# AS91-Rel8TstAd-01.net
KiCad netlist of a schematic drawn in EAGLE
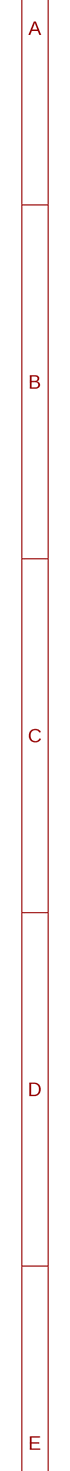
[diagram p0: schematic, sheet 1, part 1 of 2]
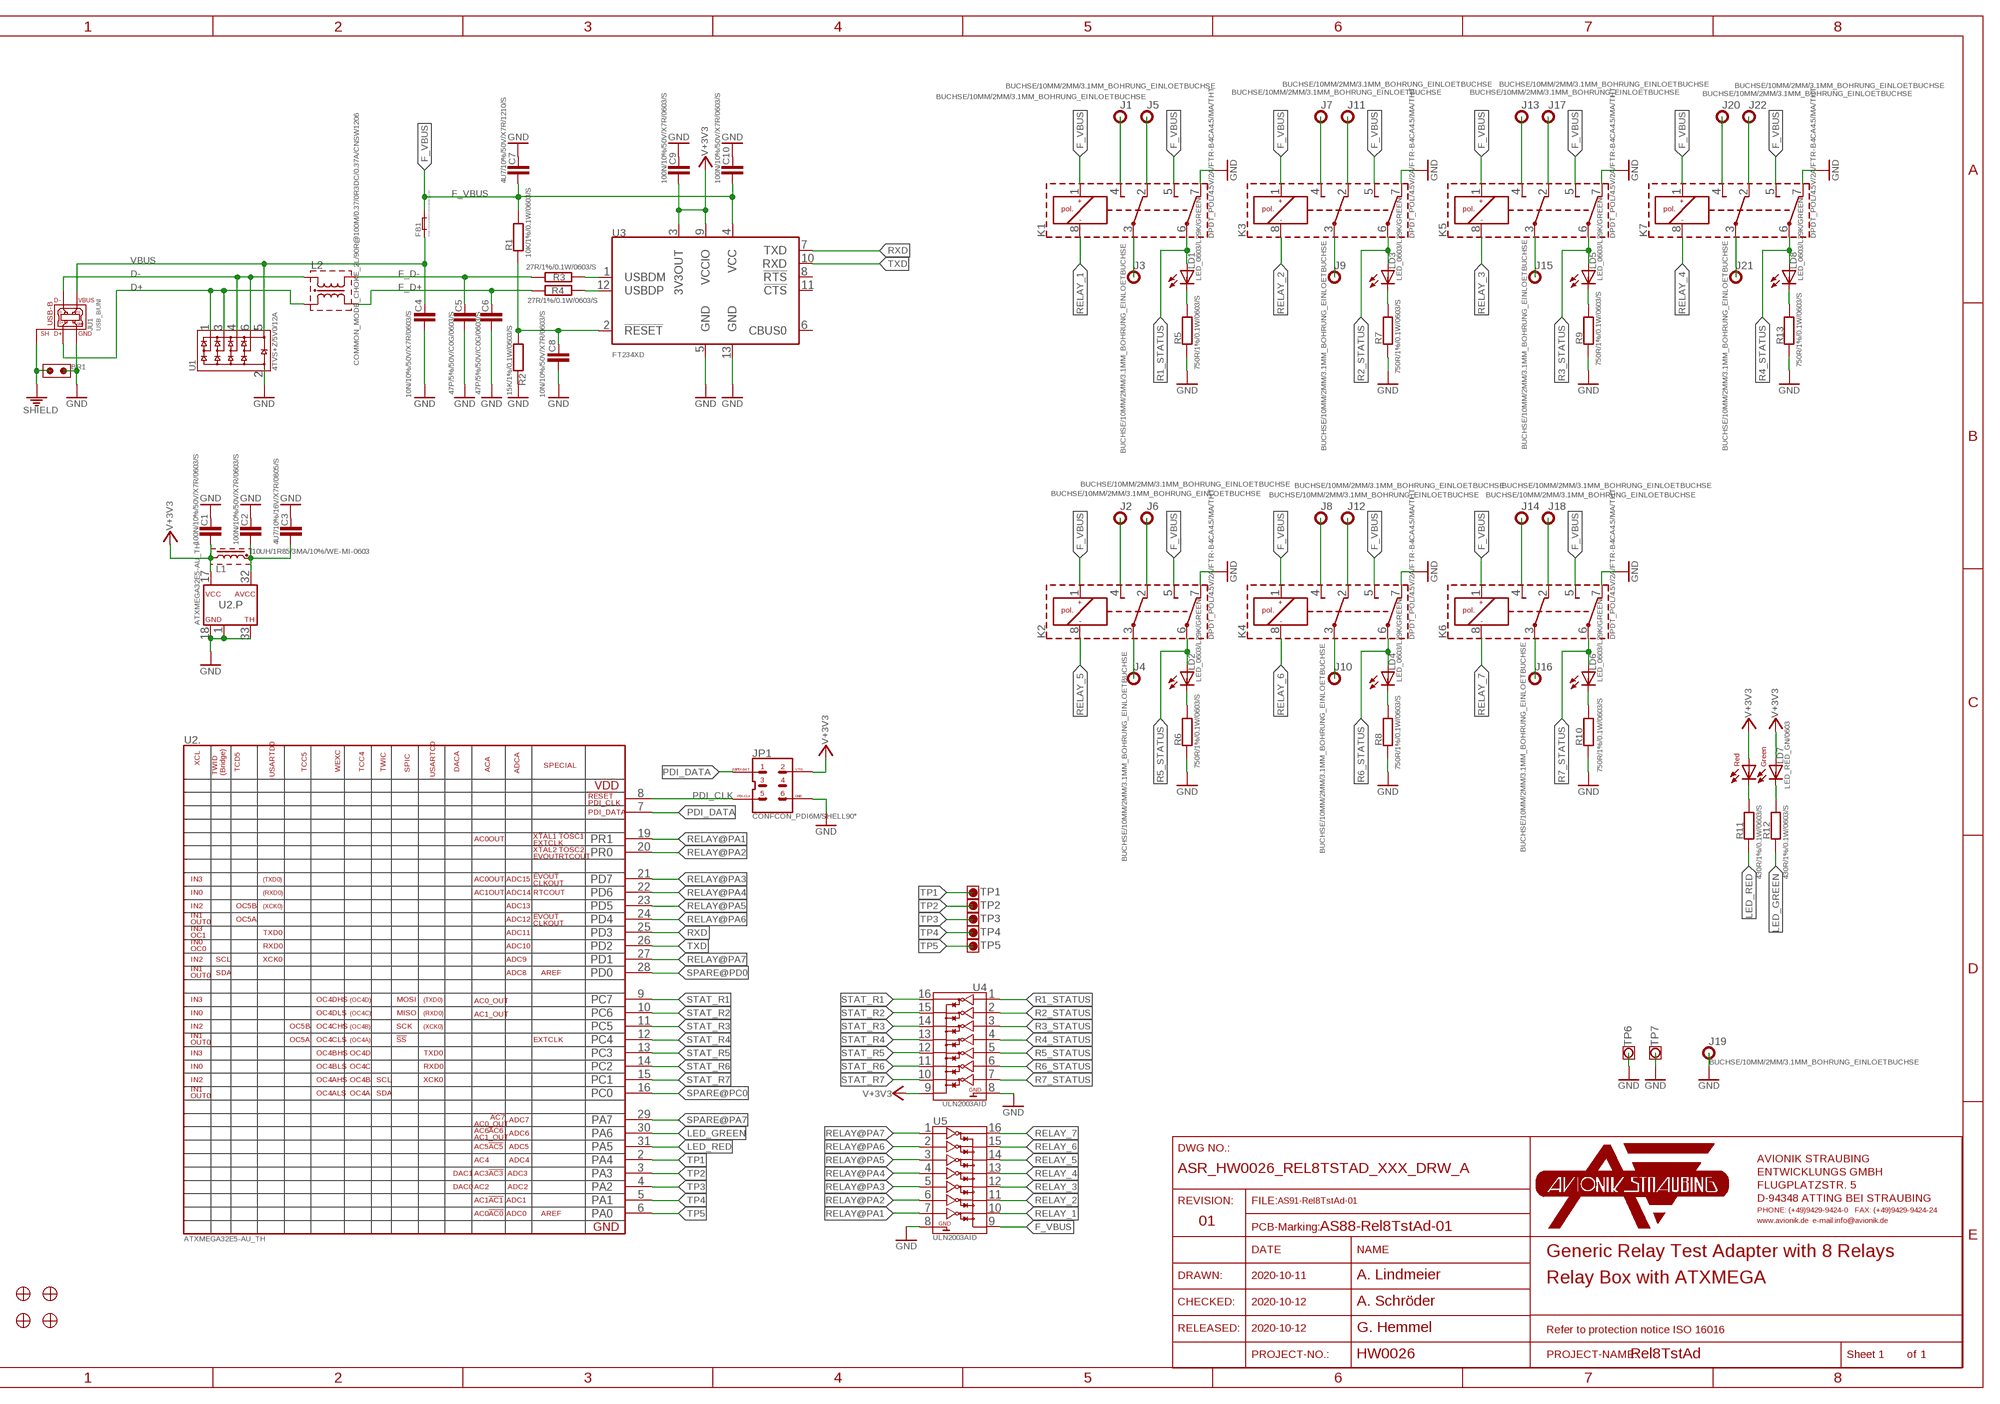
[diagram p1: schematic, sheet 1, part 2 of 2]

(export (version "E")
  (design (tool "Eeschema 10.0.6"))
  (components
    (comp (ref "BR1")
      (value "BRIDGE_OPEN/SOLDER")
      (footprint "eagle-import:SOLDER_OPEN")
      (libsource (lib "eagle-import") (part "BRIDGE_OPEN/SOLDER"))
    )
    (comp (ref "C1")
      (value "100N/10%/50V/X7R/0603/S")
      (footprint "eagle-import:C0603_STD")
      (fields (field (name "MFR") "Kemet, C0603C104K5RACTU"))
      (libsource (lib "eagle-import") (part "100N/0603/S/10%/50V/X7R"))
    )
    (comp (ref "C2")
      (value "100N/10%/50V/X7R/0603/S")
      (footprint "eagle-import:C0603_STD")
      (fields (field (name "MFR") "Kemet, C0603C104K5RACTU"))
      (libsource (lib "eagle-import") (part "100N/0603/S/10%/50V/X7R"))
    )
    (comp (ref "C3")
      (value "4U7/10%/16V/X7R/0805/S")
      (footprint "eagle-import:C0805_STD")
      (fields (field (name "MFR") "Kemet, C0805C475K4RACAUTO"))
      (libsource (lib "eagle-import") (part "4U7/0805/S/10%/16V/X7R"))
    )
    (comp (ref "C4")
      (value "10N/10%/50V/X7R/0603/S")
      (footprint "eagle-import:C0603_STD")
      (fields (field (name "MFR") "Kemet, C0603C103K5RACTU"))
      (libsource (lib "eagle-import") (part "10N/0603/S/10%/50V/X7R"))
    )
    (comp (ref "C5")
      (value "47P/5%/50V/C0G/0603/S")
      (footprint "eagle-import:C0603_STD")
      (fields (field (name "MFR") "Kemet, C0603C470J5GACAUTO"))
      (libsource (lib "eagle-import") (part "47P/0603/S/5%/50V/C0G"))
    )
    (comp (ref "C6")
      (value "47P/5%/50V/C0G/0603/S")
      (footprint "eagle-import:C0603_STD")
      (fields (field (name "MFR") "Kemet, C0603C470J5GACAUTO"))
      (libsource (lib "eagle-import") (part "47P/0603/S/5%/50V/C0G"))
    )
    (comp (ref "C7")
      (value "4U7/10%/50V/X7R/1210/S")
      (footprint "eagle-import:C1210_STD")
      (fields (field (name "MFR") "Kemet, C1210X475K5RACTU"))
      (libsource (lib "eagle-import") (part "4U7/1210/S/10%/50V/X7R"))
    )
    (comp (ref "C8")
      (value "10N/10%/50V/X7R/0603/S")
      (footprint "eagle-import:C0603_STD")
      (fields (field (name "MFR") "Kemet, C0603C103K5RACTU"))
      (libsource (lib "eagle-import") (part "10N/0603/S/10%/50V/X7R"))
    )
    (comp (ref "C9")
      (value "100N/10%/50V/X7R/0603/S")
      (footprint "eagle-import:C0603_STD")
      (fields (field (name "MFR") "Kemet, C0603C104K5RACTU"))
      (libsource (lib "eagle-import") (part "100N/0603/S/10%/50V/X7R"))
    )
    (comp (ref "C10")
      (value "100N/10%/50V/X7R/0603/S")
      (footprint "eagle-import:C0603_STD")
      (fields (field (name "MFR") "Kemet, C0603C104K5RACTU"))
      (libsource (lib "eagle-import") (part "100N/0603/S/10%/50V/X7R"))
    )
    (comp (ref "DRAWING_FRAME1")
      (value "DIN_A3LOC_PCBMARK_ASR/TOP/STOP/0.8")
      (footprint "eagle-import:FRAME_REVISION_TOP_STOP_0.8")
      (fields (field (name "PCB_MARKING") "AS88-Rel8TstAd-01"))
      (libsource (lib "eagle-import") (part "DIN_A3LOC_PCBMARK_ASR/TOP/STOP/0.8"))
    )
    (comp (ref "FB1")
      (value "FB/WE-CBF/742792620/DC0R15/0.5A/WE/CBF0603")
      (footprint "eagle-import:WE_CBF_0603")
      (fields (field (name "MFR") "Würth, 742792620"))
      (libsource (lib "eagle-import") (part "FB/WE/CBF0603/WE-CBF/742792620/DC0R15/0.5A"))
    )
    (comp (ref "J1")
      (value "BUCHSE/10MM/2MM/3.1MM_BOHRUNG_EINLOETBUCHSE")
      (footprint "eagle-import:BUCHSE2MM_PCB3.1MMDRILL")
      (fields (field (name "MFR") "MC/Stäubli, LB2-D"))
      (libsource (lib "eagle-import") (part "BUCHSE/2MM/3.1MM_BOHRUNG_EINLOETBUCHSE/10MM"))
    )
    (comp (ref "J2")
      (value "BUCHSE/10MM/2MM/3.1MM_BOHRUNG_EINLOETBUCHSE")
      (footprint "eagle-import:BUCHSE2MM_PCB3.1MMDRILL")
      (fields (field (name "MFR") "MC/Stäubli, LB2-D"))
      (libsource (lib "eagle-import") (part "BUCHSE/2MM/3.1MM_BOHRUNG_EINLOETBUCHSE/10MM"))
    )
    (comp (ref "J3")
      (value "BUCHSE/10MM/2MM/3.1MM_BOHRUNG_EINLOETBUCHSE")
      (footprint "eagle-import:BUCHSE2MM_PCB3.1MMDRILL")
      (fields (field (name "MFR") "MC/Stäubli, LB2-D"))
      (libsource (lib "eagle-import") (part "BUCHSE/2MM/3.1MM_BOHRUNG_EINLOETBUCHSE/10MM"))
    )
    (comp (ref "J4")
      (value "BUCHSE/10MM/2MM/3.1MM_BOHRUNG_EINLOETBUCHSE")
      (footprint "eagle-import:BUCHSE2MM_PCB3.1MMDRILL")
      (fields (field (name "MFR") "MC/Stäubli, LB2-D"))
      (libsource (lib "eagle-import") (part "BUCHSE/2MM/3.1MM_BOHRUNG_EINLOETBUCHSE/10MM"))
    )
    (comp (ref "J5")
      (value "BUCHSE/10MM/2MM/3.1MM_BOHRUNG_EINLOETBUCHSE")
      (footprint "eagle-import:BUCHSE2MM_PCB3.1MMDRILL")
      (fields (field (name "MFR") "MC/Stäubli, LB2-D"))
      (libsource (lib "eagle-import") (part "BUCHSE/2MM/3.1MM_BOHRUNG_EINLOETBUCHSE/10MM"))
    )
    (comp (ref "J6")
      (value "BUCHSE/10MM/2MM/3.1MM_BOHRUNG_EINLOETBUCHSE")
      (footprint "eagle-import:BUCHSE2MM_PCB3.1MMDRILL")
      (fields (field (name "MFR") "MC/Stäubli, LB2-D"))
      (libsource (lib "eagle-import") (part "BUCHSE/2MM/3.1MM_BOHRUNG_EINLOETBUCHSE/10MM"))
    )
    (comp (ref "J7")
      (value "BUCHSE/10MM/2MM/3.1MM_BOHRUNG_EINLOETBUCHSE")
      (footprint "eagle-import:BUCHSE2MM_PCB3.1MMDRILL")
      (fields (field (name "MFR") "MC/Stäubli, LB2-D"))
      (libsource (lib "eagle-import") (part "BUCHSE/2MM/3.1MM_BOHRUNG_EINLOETBUCHSE/10MM"))
    )
    (comp (ref "J8")
      (value "BUCHSE/10MM/2MM/3.1MM_BOHRUNG_EINLOETBUCHSE")
      (footprint "eagle-import:BUCHSE2MM_PCB3.1MMDRILL")
      (fields (field (name "MFR") "MC/Stäubli, LB2-D"))
      (libsource (lib "eagle-import") (part "BUCHSE/2MM/3.1MM_BOHRUNG_EINLOETBUCHSE/10MM"))
    )
    (comp (ref "J9")
      (value "BUCHSE/10MM/2MM/3.1MM_BOHRUNG_EINLOETBUCHSE")
      (footprint "eagle-import:BUCHSE2MM_PCB3.1MMDRILL")
      (fields (field (name "MFR") "MC/Stäubli, LB2-D"))
      (libsource (lib "eagle-import") (part "BUCHSE/2MM/3.1MM_BOHRUNG_EINLOETBUCHSE/10MM"))
    )
    (comp (ref "J10")
      (value "BUCHSE/10MM/2MM/3.1MM_BOHRUNG_EINLOETBUCHSE")
      (footprint "eagle-import:BUCHSE2MM_PCB3.1MMDRILL")
      (fields (field (name "MFR") "MC/Stäubli, LB2-D"))
      (libsource (lib "eagle-import") (part "BUCHSE/2MM/3.1MM_BOHRUNG_EINLOETBUCHSE/10MM"))
    )
    (comp (ref "J11")
      (value "BUCHSE/10MM/2MM/3.1MM_BOHRUNG_EINLOETBUCHSE")
      (footprint "eagle-import:BUCHSE2MM_PCB3.1MMDRILL")
      (fields (field (name "MFR") "MC/Stäubli, LB2-D"))
      (libsource (lib "eagle-import") (part "BUCHSE/2MM/3.1MM_BOHRUNG_EINLOETBUCHSE/10MM"))
    )
    (comp (ref "J12")
      (value "BUCHSE/10MM/2MM/3.1MM_BOHRUNG_EINLOETBUCHSE")
      (footprint "eagle-import:BUCHSE2MM_PCB3.1MMDRILL")
      (fields (field (name "MFR") "MC/Stäubli, LB2-D"))
      (libsource (lib "eagle-import") (part "BUCHSE/2MM/3.1MM_BOHRUNG_EINLOETBUCHSE/10MM"))
    )
    (comp (ref "J13")
      (value "BUCHSE/10MM/2MM/3.1MM_BOHRUNG_EINLOETBUCHSE")
      (footprint "eagle-import:BUCHSE2MM_PCB3.1MMDRILL")
      (fields (field (name "MFR") "MC/Stäubli, LB2-D"))
      (libsource (lib "eagle-import") (part "BUCHSE/2MM/3.1MM_BOHRUNG_EINLOETBUCHSE/10MM"))
    )
    (comp (ref "J14")
      (value "BUCHSE/10MM/2MM/3.1MM_BOHRUNG_EINLOETBUCHSE")
      (footprint "eagle-import:BUCHSE2MM_PCB3.1MMDRILL")
      (fields (field (name "MFR") "MC/Stäubli, LB2-D"))
      (libsource (lib "eagle-import") (part "BUCHSE/2MM/3.1MM_BOHRUNG_EINLOETBUCHSE/10MM"))
    )
    (comp (ref "J15")
      (value "BUCHSE/10MM/2MM/3.1MM_BOHRUNG_EINLOETBUCHSE")
      (footprint "eagle-import:BUCHSE2MM_PCB3.1MMDRILL")
      (fields (field (name "MFR") "MC/Stäubli, LB2-D"))
      (libsource (lib "eagle-import") (part "BUCHSE/2MM/3.1MM_BOHRUNG_EINLOETBUCHSE/10MM"))
    )
    (comp (ref "J16")
      (value "BUCHSE/10MM/2MM/3.1MM_BOHRUNG_EINLOETBUCHSE")
      (footprint "eagle-import:BUCHSE2MM_PCB3.1MMDRILL")
      (fields (field (name "MFR") "MC/Stäubli, LB2-D"))
      (libsource (lib "eagle-import") (part "BUCHSE/2MM/3.1MM_BOHRUNG_EINLOETBUCHSE/10MM"))
    )
    (comp (ref "J17")
      (value "BUCHSE/10MM/2MM/3.1MM_BOHRUNG_EINLOETBUCHSE")
      (footprint "eagle-import:BUCHSE2MM_PCB3.1MMDRILL")
      (fields (field (name "MFR") "MC/Stäubli, LB2-D"))
      (libsource (lib "eagle-import") (part "BUCHSE/2MM/3.1MM_BOHRUNG_EINLOETBUCHSE/10MM"))
    )
    (comp (ref "J18")
      (value "BUCHSE/10MM/2MM/3.1MM_BOHRUNG_EINLOETBUCHSE")
      (footprint "eagle-import:BUCHSE2MM_PCB3.1MMDRILL")
      (fields (field (name "MFR") "MC/Stäubli, LB2-D"))
      (libsource (lib "eagle-import") (part "BUCHSE/2MM/3.1MM_BOHRUNG_EINLOETBUCHSE/10MM"))
    )
    (comp (ref "J19")
      (value "BUCHSE/10MM/2MM/3.1MM_BOHRUNG_EINLOETBUCHSE")
      (footprint "eagle-import:BUCHSE2MM_PCB3.1MMDRILL")
      (fields (field (name "MFR") "MC/Stäubli, LB2-D"))
      (libsource (lib "eagle-import") (part "BUCHSE/2MM/3.1MM_BOHRUNG_EINLOETBUCHSE/10MM"))
    )
    (comp (ref "J20")
      (value "BUCHSE/10MM/2MM/3.1MM_BOHRUNG_EINLOETBUCHSE")
      (footprint "eagle-import:BUCHSE2MM_PCB3.1MMDRILL")
      (fields (field (name "MFR") "MC/Stäubli, LB2-D"))
      (libsource (lib "eagle-import") (part "BUCHSE/2MM/3.1MM_BOHRUNG_EINLOETBUCHSE/10MM"))
    )
    (comp (ref "J21")
      (value "BUCHSE/10MM/2MM/3.1MM_BOHRUNG_EINLOETBUCHSE")
      (footprint "eagle-import:BUCHSE2MM_PCB3.1MMDRILL")
      (fields (field (name "MFR") "MC/Stäubli, LB2-D"))
      (libsource (lib "eagle-import") (part "BUCHSE/2MM/3.1MM_BOHRUNG_EINLOETBUCHSE/10MM"))
    )
    (comp (ref "J22")
      (value "BUCHSE/10MM/2MM/3.1MM_BOHRUNG_EINLOETBUCHSE")
      (footprint "eagle-import:BUCHSE2MM_PCB3.1MMDRILL")
      (fields (field (name "MFR") "MC/Stäubli, LB2-D"))
      (libsource (lib "eagle-import") (part "BUCHSE/2MM/3.1MM_BOHRUNG_EINLOETBUCHSE/10MM"))
    )
    (comp (ref "JP1")
      (value "CONFCON_PDI6M/SHELL90°")
      (footprint "eagle-import:PH2X3_WSL_SHELL_90°")
      (fields (field (name "MFR") "Molex, 90130-3106"))
      (libsource (lib "eagle-import") (part "CONFCON_PDI6M/SHELL90°"))
    )
    (comp (ref "JU1")
      (value "USB_B/UNI")
      (footprint "eagle-import:USB-B-BUCHSE-LP")
      (fields (field (name "MFR") "Amphenol, 61729-0010BLF"))
      (libsource (lib "eagle-import") (part "USB_B/UNI"))
    )
    (comp (ref "K1")
      (value "DPDT_POL/4.5V/2A/FTR-B4CA4.5/MA/THT")
      (footprint "eagle-import:FTR-B4")
      (fields (field (name "MFR") "Fujitsu-Takamisawa, FTR-B4CA4.5"))
      (libsource (lib "eagle-import") (part "DPDT_POL/MA/THT/4.5V/2A/FTR-B4CA4.5"))
    )
    (comp (ref "K2")
      (value "DPDT_POL/4.5V/2A/FTR-B4CA4.5/MA/THT")
      (footprint "eagle-import:FTR-B4")
      (fields (field (name "MFR") "Fujitsu-Takamisawa, FTR-B4CA4.5"))
      (libsource (lib "eagle-import") (part "DPDT_POL/MA/THT/4.5V/2A/FTR-B4CA4.5"))
    )
    (comp (ref "K3")
      (value "DPDT_POL/4.5V/2A/FTR-B4CA4.5/MA/THT")
      (footprint "eagle-import:FTR-B4")
      (fields (field (name "MFR") "Fujitsu-Takamisawa, FTR-B4CA4.5"))
      (libsource (lib "eagle-import") (part "DPDT_POL/MA/THT/4.5V/2A/FTR-B4CA4.5"))
    )
    (comp (ref "K4")
      (value "DPDT_POL/4.5V/2A/FTR-B4CA4.5/MA/THT")
      (footprint "eagle-import:FTR-B4")
      (fields (field (name "MFR") "Fujitsu-Takamisawa, FTR-B4CA4.5"))
      (libsource (lib "eagle-import") (part "DPDT_POL/MA/THT/4.5V/2A/FTR-B4CA4.5"))
    )
    (comp (ref "K5")
      (value "DPDT_POL/4.5V/2A/FTR-B4CA4.5/MA/THT")
      (footprint "eagle-import:FTR-B4")
      (fields (field (name "MFR") "Fujitsu-Takamisawa, FTR-B4CA4.5"))
      (libsource (lib "eagle-import") (part "DPDT_POL/MA/THT/4.5V/2A/FTR-B4CA4.5"))
    )
    (comp (ref "K6")
      (value "DPDT_POL/4.5V/2A/FTR-B4CA4.5/MA/THT")
      (footprint "eagle-import:FTR-B4")
      (fields (field (name "MFR") "Fujitsu-Takamisawa, FTR-B4CA4.5"))
      (libsource (lib "eagle-import") (part "DPDT_POL/MA/THT/4.5V/2A/FTR-B4CA4.5"))
    )
    (comp (ref "K7")
      (value "DPDT_POL/4.5V/2A/FTR-B4CA4.5/MA/THT")
      (footprint "eagle-import:FTR-B4")
      (fields (field (name "MFR") "Fujitsu-Takamisawa, FTR-B4CA4.5"))
      (libsource (lib "eagle-import") (part "DPDT_POL/MA/THT/4.5V/2A/FTR-B4CA4.5"))
    )
    (comp (ref "L1")
      (value "10UH/1R85/3MA/10%/WE-MI-0603")
      (footprint "eagle-import:WE-MI_0603")
      (fields (field (name "MFR") "Würth, 7447968"))
      (libsource (lib "eagle-import") (part "10UH/WE-MI-0603/1R85/3MA/10%"))
    )
    (comp (ref "L2")
      (value "COMMON_MODE_CHOKE_2L/90R@100M/0.37/0R3DC/0.37A/CNSW1206")
      (footprint "eagle-import:WUERTH_CNSW_1206")
      (fields (field (name "MFR") "Würth, 744232090"))
      (libsource (lib "eagle-import") (part "COMMON_MODE_CHOKE_2L/CNSW1206/90R@100M/0.37/0R3DC/0.37A"))
    )
    (comp (ref "LD1")
      (value "LED_0603/L29K/GREEN")
      (footprint "eagle-import:CHIPLED0603SMALL")
      (fields (field (name "MFR") "Osram, LG L29K-F2J1-24-Z"))
      (libsource (lib "eagle-import") (part "LED_0603/L29K/GREEN"))
    )
    (comp (ref "LD2")
      (value "LED_0603/L29K/GREEN")
      (footprint "eagle-import:CHIPLED0603SMALL")
      (fields (field (name "MFR") "Osram, LG L29K-F2J1-24-Z"))
      (libsource (lib "eagle-import") (part "LED_0603/L29K/GREEN"))
    )
    (comp (ref "LD3")
      (value "LED_0603/L29K/GREEN")
      (footprint "eagle-import:CHIPLED0603SMALL")
      (fields (field (name "MFR") "Osram, LG L29K-F2J1-24-Z"))
      (libsource (lib "eagle-import") (part "LED_0603/L29K/GREEN"))
    )
    (comp (ref "LD4")
      (value "LED_0603/L29K/GREEN")
      (footprint "eagle-import:CHIPLED0603SMALL")
      (fields (field (name "MFR") "Osram, LG L29K-F2J1-24-Z"))
      (libsource (lib "eagle-import") (part "LED_0603/L29K/GREEN"))
    )
    (comp (ref "LD5")
      (value "LED_0603/L29K/GREEN")
      (footprint "eagle-import:CHIPLED0603SMALL")
      (fields (field (name "MFR") "Osram, LG L29K-F2J1-24-Z"))
      (libsource (lib "eagle-import") (part "LED_0603/L29K/GREEN"))
    )
    (comp (ref "LD6")
      (value "LED_0603/L29K/GREEN")
      (footprint "eagle-import:CHIPLED0603SMALL")
      (fields (field (name "MFR") "Osram, LG L29K-F2J1-24-Z"))
      (libsource (lib "eagle-import") (part "LED_0603/L29K/GREEN"))
    )
    (comp (ref "LD7")
      (value "LED_RED_GN/0603")
      (footprint "eagle-import:DUOLED_0603")
      (fields (field (name "MFR") "Broadcom/Avago, HSMF-C165"))
      (libsource (lib "eagle-import") (part "LED_RED_GN/0603"))
    )
    (comp (ref "LD8")
      (value "LED_0603/L29K/GREEN")
      (footprint "eagle-import:CHIPLED0603SMALL")
      (fields (field (name "MFR") "Osram, LG L29K-F2J1-24-Z"))
      (libsource (lib "eagle-import") (part "LED_0603/L29K/GREEN"))
    )
    (comp (ref "PCB1")
      (value "TEKO_MOD_P2")
      (footprint "eagle-import:BOARD_TEKO_MOD_P2_UP")
      (fields (field (name "MFR") "TEKO, P2.10"))
      (libsource (lib "eagle-import") (part "TEKO_MOD_P2"))
    )
    (comp (ref "R1")
      (value "10K/1%/0.1W/0603/S")
      (footprint "eagle-import:R0603_STD")
      (fields (field (name "MFR") "Vishay, CRCW060310K0FKEA"))
      (libsource (lib "eagle-import") (part "10K/0603/S/1%/0.1W"))
    )
    (comp (ref "R2")
      (value "15K/1%/0.1W/0603/S")
      (footprint "eagle-import:R0603_STD")
      (fields (field (name "MFR") "Vishay, CRCW060315K0FKEA"))
      (libsource (lib "eagle-import") (part "15K/0603/S/1%/0.1W"))
    )
    (comp (ref "R3")
      (value "27R/1%/0.1W/0603/S")
      (footprint "eagle-import:R0603_STD")
      (fields (field (name "MFR") "Vishay, CRCW060327R0FKEA"))
      (libsource (lib "eagle-import") (part "27R/0603/S/1%/0.1W"))
    )
    (comp (ref "R4")
      (value "27R/1%/0.1W/0603/S")
      (footprint "eagle-import:R0603_STD")
      (fields (field (name "MFR") "Vishay, CRCW060327R0FKEA"))
      (libsource (lib "eagle-import") (part "27R/0603/S/1%/0.1W"))
    )
    (comp (ref "R5")
      (value "750R/1%/0.1W/0603/S")
      (footprint "eagle-import:R0603_STD")
      (libsource (lib "eagle-import") (part "750R/0603/S/1%/0.1W"))
    )
    (comp (ref "R6")
      (value "750R/1%/0.1W/0603/S")
      (footprint "eagle-import:R0603_STD")
      (libsource (lib "eagle-import") (part "750R/0603/S/1%/0.1W"))
    )
    (comp (ref "R7")
      (value "750R/1%/0.1W/0603/S")
      (footprint "eagle-import:R0603_STD")
      (libsource (lib "eagle-import") (part "750R/0603/S/1%/0.1W"))
    )
    (comp (ref "R8")
      (value "750R/1%/0.1W/0603/S")
      (footprint "eagle-import:R0603_STD")
      (libsource (lib "eagle-import") (part "750R/0603/S/1%/0.1W"))
    )
    (comp (ref "R9")
      (value "750R/1%/0.1W/0603/S")
      (footprint "eagle-import:R0603_STD")
      (libsource (lib "eagle-import") (part "750R/0603/S/1%/0.1W"))
    )
    (comp (ref "R10")
      (value "750R/1%/0.1W/0603/S")
      (footprint "eagle-import:R0603_STD")
      (libsource (lib "eagle-import") (part "750R/0603/S/1%/0.1W"))
    )
    (comp (ref "R11")
      (value "430R/1%/0.1W/0603/S")
      (footprint "eagle-import:R0603_STD")
      (fields (field (name "MFR") "Vishay, CRCW0603430RFKEA"))
      (libsource (lib "eagle-import") (part "430R/0603/S/1%/0.1W"))
    )
    (comp (ref "R12")
      (value "430R/1%/0.1W/0603/S")
      (footprint "eagle-import:R0603_STD")
      (fields (field (name "MFR") "Vishay, CRCW0603430RFKEA"))
      (libsource (lib "eagle-import") (part "430R/0603/S/1%/0.1W"))
    )
    (comp (ref "R13")
      (value "750R/1%/0.1W/0603/S")
      (footprint "eagle-import:R0603_STD")
      (libsource (lib "eagle-import") (part "750R/0603/S/1%/0.1W"))
    )
    (comp (ref "TP1")
      (value "TESTPAD_ROUND/1.0MM")
      (footprint "eagle-import:TP_ROUND_SMD_1MM")
      (libsource (lib "eagle-import") (part "TESTPAD_ROUND/1.0MM"))
    )
    (comp (ref "TP2")
      (value "TESTPAD_ROUND/1.0MM")
      (footprint "eagle-import:TP_ROUND_SMD_1MM")
      (libsource (lib "eagle-import") (part "TESTPAD_ROUND/1.0MM"))
    )
    (comp (ref "TP3")
      (value "TESTPAD_ROUND/1.0MM")
      (footprint "eagle-import:TP_ROUND_SMD_1MM")
      (libsource (lib "eagle-import") (part "TESTPAD_ROUND/1.0MM"))
    )
    (comp (ref "TP4")
      (value "TESTPAD_ROUND/1.0MM")
      (footprint "eagle-import:TP_ROUND_SMD_1MM")
      (libsource (lib "eagle-import") (part "TESTPAD_ROUND/1.0MM"))
    )
    (comp (ref "TP5")
      (value "TESTPAD_ROUND/1.0MM")
      (footprint "eagle-import:TP_ROUND_SMD_1MM")
      (libsource (lib "eagle-import") (part "TESTPAD_ROUND/1.0MM"))
    )
    (comp (ref "TP6")
      (value "TESTPOINT_1/OCT_0.8")
      (footprint "eagle-import:TP_OCT_0.8_DRILL")
      (libsource (lib "eagle-import") (part "TESTPOINT_1/OCT_0.8"))
    )
    (comp (ref "TP7")
      (value "TESTPOINT_1/OCT_0.8")
      (footprint "eagle-import:TP_OCT_0.8_DRILL")
      (libsource (lib "eagle-import") (part "TESTPOINT_1/OCT_0.8"))
    )
    (comp (ref "U1")
      (value "4TVS+Z/5V0/12A")
      (footprint "eagle-import:SOT23-6L")
      (fields (field (name "MFR") "Würth, 824015"))
      (libsource (lib "eagle-import") (part "4TVS+Z/5V0/12A"))
    )
    (comp (ref "U2")
      (value "ATXMEGA32E5-AU_TH")
      (footprint "eagle-import:TQFP32A_THGND")
      (fields (field (name "MFR") "Microchip/Atmel, ATXMEGA32E5-AU"))
      (libsource (lib "eagle-import") (part "ATXMEGAE5-AU_TH32"))
    )
    (comp (ref "U3")
      (value "FT234XD")
      (footprint "eagle-import:FT234XD")
      (fields (field (name "MFR") "FTDI, FT234XD-R"))
      (libsource (lib "eagle-import") (part "FT234XD"))
    )
    (comp (ref "U4")
      (value "ULN2003AID")
      (footprint "eagle-import:SO16")
      (fields (field (name "MFR") "TI, ULN2003AID"))
      (libsource (lib "eagle-import") (part "ULN2003DAI"))
    )
    (comp (ref "U5")
      (value "ULN2003AID")
      (footprint "eagle-import:SO16")
      (fields (field (name "MFR") "TI, ULN2003AID"))
      (libsource (lib "eagle-import") (part "ULN2003DAI"))
    )
  )
  (nets
    (net (code "1") (name "/D+") (class "Default")
      (node (ref "JU1") (pin "3") (pinfunction "D+_3") (pintype "bidirectional"))
      (node (ref "L2") (pin "1") (pinfunction "L2_A_1") (pintype "passive"))
      (node (ref "U1") (pin "1") (pinfunction "IO1_1") (pintype "passive"))
      (node (ref "U1") (pin "3") (pinfunction "IO2_3") (pintype "passive"))
    )
    (net (code "2") (name "/D-") (class "Default")
      (node (ref "JU1") (pin "2") (pinfunction "D-_2") (pintype "bidirectional"))
      (node (ref "L2") (pin "4") (pinfunction "L1_A_4") (pintype "passive"))
      (node (ref "U1") (pin "4") (pinfunction "IO3_4") (pintype "passive"))
      (node (ref "U1") (pin "6") (pinfunction "IO4_6") (pintype "passive"))
    )
    (net (code "3") (name "/F_D+") (class "Default")
      (node (ref "C6") (pin "1") (pinfunction "1_1") (pintype "passive"))
      (node (ref "L2") (pin "2") (pinfunction "L2_B_2") (pintype "passive"))
      (node (ref "R4") (pin "1") (pinfunction "1_1") (pintype "passive"))
    )
    (net (code "4") (name "/F_D-") (class "Default")
      (node (ref "C5") (pin "1") (pinfunction "1_1") (pintype "passive"))
      (node (ref "L2") (pin "3") (pinfunction "L1_B_3") (pintype "passive"))
      (node (ref "R3") (pin "1") (pinfunction "1_1") (pintype "passive"))
    )
    (net (code "5") (name "/PDI_CLK") (class "Default")
      (node (ref "JP1") (pin "5") (pinfunction "PDI_CLK_5") (pintype "bidirectional"))
      (node (ref "U2") (pin "8") (pinfunction "PDI_CLK/~{RESET}_8") (pintype "input"))
    )
    (net (code "6") (name "/VBUS") (class "Default")
      (node (ref "C4") (pin "1") (pinfunction "1_1") (pintype "passive"))
      (node (ref "FB1") (pin "1") (pinfunction "1_1") (pintype "passive"))
      (node (ref "JU1") (pin "1") (pinfunction "VBUS_1") (pintype "power_in"))
      (node (ref "U1") (pin "5") (pinfunction "VDD_5") (pintype "passive"))
    )
    (net (code "7") (name "F_VBUS") (class "Default")
      (node (ref "C10") (pin "2") (pinfunction "2_2") (pintype "passive"))
      (node (ref "C7") (pin "2") (pinfunction "2_2") (pintype "passive"))
      (node (ref "FB1") (pin "2") (pinfunction "2_2") (pintype "passive"))
      (node (ref "K1") (pin "1") (pinfunction "K+_1") (pintype "passive"))
      (node (ref "K1") (pin "5") (pinfunction "NO2_5") (pintype "passive"))
      (node (ref "K2") (pin "1") (pinfunction "K+_1") (pintype "passive"))
      (node (ref "K2") (pin "5") (pinfunction "NO2_5") (pintype "passive"))
      (node (ref "K3") (pin "1") (pinfunction "K+_1") (pintype "passive"))
      (node (ref "K3") (pin "5") (pinfunction "NO2_5") (pintype "passive"))
      (node (ref "K4") (pin "1") (pinfunction "K+_1") (pintype "passive"))
      (node (ref "K4") (pin "5") (pinfunction "NO2_5") (pintype "passive"))
      (node (ref "K5") (pin "1") (pinfunction "K+_1") (pintype "passive"))
      (node (ref "K5") (pin "5") (pinfunction "NO2_5") (pintype "passive"))
      (node (ref "K6") (pin "1") (pinfunction "K+_1") (pintype "passive"))
      (node (ref "K6") (pin "5") (pinfunction "NO2_5") (pintype "passive"))
      (node (ref "K7") (pin "1") (pinfunction "K+_1") (pintype "passive"))
      (node (ref "K7") (pin "5") (pinfunction "NO2_5") (pintype "passive"))
      (node (ref "R1") (pin "2") (pinfunction "2_2") (pintype "passive"))
      (node (ref "U3") (pin "4") (pinfunction "VCC_4") (pintype "power_in"))
      (node (ref "U5") (pin "9") (pinfunction "CFW_9") (pintype "passive"))
    )
    (net (code "8") (name "GND") (class "Default")
      (node (ref "BR1") (pin "CENT") (pinfunction "CENT_CENT") (pintype "passive"))
      (node (ref "C1") (pin "1") (pinfunction "1_1") (pintype "passive"))
      (node (ref "C10") (pin "1") (pinfunction "1_1") (pintype "passive"))
      (node (ref "C2") (pin "1") (pinfunction "1_1") (pintype "passive"))
      (node (ref "C3") (pin "1") (pinfunction "1_1") (pintype "passive"))
      (node (ref "C4") (pin "2") (pinfunction "2_2") (pintype "passive"))
      (node (ref "C5") (pin "2") (pinfunction "2_2") (pintype "passive"))
      (node (ref "C6") (pin "2") (pinfunction "2_2") (pintype "passive"))
      (node (ref "C7") (pin "1") (pinfunction "1_1") (pintype "passive"))
      (node (ref "C8") (pin "2") (pinfunction "2_2") (pintype "passive"))
      (node (ref "C9") (pin "1") (pinfunction "1_1") (pintype "passive"))
      (node (ref "J19") (pin "1") (pinfunction "1_1") (pintype "passive"))
      (node (ref "JP1") (pin "6") (pinfunction "GND_6") (pintype "power_in"))
      (node (ref "JU1") (pin "4") (pinfunction "GND_4") (pintype "power_in"))
      (node (ref "K1") (pin "7") (pinfunction "NC2_7") (pintype "passive"))
      (node (ref "K2") (pin "7") (pinfunction "NC2_7") (pintype "passive"))
      (node (ref "K3") (pin "7") (pinfunction "NC2_7") (pintype "passive"))
      (node (ref "K4") (pin "7") (pinfunction "NC2_7") (pintype "passive"))
      (node (ref "K5") (pin "7") (pinfunction "NC2_7") (pintype "passive"))
      (node (ref "K6") (pin "7") (pinfunction "NC2_7") (pintype "passive"))
      (node (ref "K7") (pin "7") (pinfunction "NC2_7") (pintype "passive"))
      (node (ref "R10") (pin "1") (pinfunction "1_1") (pintype "passive"))
      (node (ref "R13") (pin "1") (pinfunction "1_1") (pintype "passive"))
      (node (ref "R2") (pin "1") (pinfunction "1_1") (pintype "passive"))
      (node (ref "R5") (pin "1") (pinfunction "1_1") (pintype "passive"))
      (node (ref "R6") (pin "1") (pinfunction "1_1") (pintype "passive"))
      (node (ref "R7") (pin "1") (pinfunction "1_1") (pintype "passive"))
      (node (ref "R8") (pin "1") (pinfunction "1_1") (pintype "passive"))
      (node (ref "R9") (pin "1") (pinfunction "1_1") (pintype "passive"))
      (node (ref "TP6") (pin "A") (pinfunction "1_A") (pintype "passive"))
      (node (ref "TP7") (pin "A") (pinfunction "1_A") (pintype "passive"))
      (node (ref "U1") (pin "2") (pinfunction "GND_2") (pintype "passive"))
      (node (ref "U2") (pin "1") (pinfunction "GND_1") (pintype "power_in"))
      (node (ref "U2") (pin "18") (pinfunction "GND_18") (pintype "power_in"))
      (node (ref "U2") (pin "33") (pinfunction "GND_33") (pintype "power_in"))
      (node (ref "U3") (pin "13") (pinfunction "GND_13") (pintype "power_in"))
      (node (ref "U3") (pin "5") (pinfunction "GND_5") (pintype "power_in"))
      (node (ref "U4") (pin "8") (pinfunction "GND_8") (pintype "power_in"))
      (node (ref "U5") (pin "8") (pinfunction "GND_8") (pintype "power_in"))
    )
    (net (code "9") (name "LED_GREEN") (class "Default")
      (node (ref "R12") (pin "1") (pinfunction "1_1") (pintype "passive"))
      (node (ref "U2") (pin "30") (pinfunction "PA6_30") (pintype "bidirectional"))
    )
    (net (code "10") (name "LED_RED") (class "Default")
      (node (ref "R11") (pin "1") (pinfunction "1_1") (pintype "passive"))
      (node (ref "U2") (pin "31") (pinfunction "PA5_31") (pintype "bidirectional"))
    )
    (net (code "11") (name "Net-(K1-COM1)") (class "Default")
      (node (ref "J3") (pin "1") (pinfunction "1_1") (pintype "passive"))
      (node (ref "K1") (pin "3") (pinfunction "COM1_3") (pintype "passive"))
    )
    (net (code "12") (name "Net-(K1-NC1)") (class "Default")
      (node (ref "J5") (pin "1") (pinfunction "1_1") (pintype "passive"))
      (node (ref "K1") (pin "2") (pinfunction "NC1_2") (pintype "passive"))
    )
    (net (code "13") (name "Net-(K1-NO1)") (class "Default")
      (node (ref "J1") (pin "1") (pinfunction "1_1") (pintype "passive"))
      (node (ref "K1") (pin "4") (pinfunction "NO1_4") (pintype "passive"))
    )
    (net (code "14") (name "Net-(K2-COM1)") (class "Default")
      (node (ref "J4") (pin "1") (pinfunction "1_1") (pintype "passive"))
      (node (ref "K2") (pin "3") (pinfunction "COM1_3") (pintype "passive"))
    )
    (net (code "15") (name "Net-(K2-NC1)") (class "Default")
      (node (ref "J6") (pin "1") (pinfunction "1_1") (pintype "passive"))
      (node (ref "K2") (pin "2") (pinfunction "NC1_2") (pintype "passive"))
    )
    (net (code "16") (name "Net-(K2-NO1)") (class "Default")
      (node (ref "J2") (pin "1") (pinfunction "1_1") (pintype "passive"))
      (node (ref "K2") (pin "4") (pinfunction "NO1_4") (pintype "passive"))
    )
    (net (code "17") (name "Net-(K3-COM1)") (class "Default")
      (node (ref "J9") (pin "1") (pinfunction "1_1") (pintype "passive"))
      (node (ref "K3") (pin "3") (pinfunction "COM1_3") (pintype "passive"))
    )
    (net (code "18") (name "Net-(K3-NC1)") (class "Default")
      (node (ref "J11") (pin "1") (pinfunction "1_1") (pintype "passive"))
      (node (ref "K3") (pin "2") (pinfunction "NC1_2") (pintype "passive"))
    )
    (net (code "19") (name "Net-(K3-NO1)") (class "Default")
      (node (ref "J7") (pin "1") (pinfunction "1_1") (pintype "passive"))
      (node (ref "K3") (pin "4") (pinfunction "NO1_4") (pintype "passive"))
    )
    (net (code "20") (name "Net-(K4-COM1)") (class "Default")
      (node (ref "J10") (pin "1") (pinfunction "1_1") (pintype "passive"))
      (node (ref "K4") (pin "3") (pinfunction "COM1_3") (pintype "passive"))
    )
    (net (code "21") (name "Net-(K4-NC1)") (class "Default")
      (node (ref "J12") (pin "1") (pinfunction "1_1") (pintype "passive"))
      (node (ref "K4") (pin "2") (pinfunction "NC1_2") (pintype "passive"))
    )
    (net (code "22") (name "Net-(K4-NO1)") (class "Default")
      (node (ref "J8") (pin "1") (pinfunction "1_1") (pintype "passive"))
      (node (ref "K4") (pin "4") (pinfunction "NO1_4") (pintype "passive"))
    )
    (net (code "23") (name "Net-(K5-COM1)") (class "Default")
      (node (ref "J15") (pin "1") (pinfunction "1_1") (pintype "passive"))
      (node (ref "K5") (pin "3") (pinfunction "COM1_3") (pintype "passive"))
    )
    (net (code "24") (name "Net-(K5-NC1)") (class "Default")
      (node (ref "J17") (pin "1") (pinfunction "1_1") (pintype "passive"))
      (node (ref "K5") (pin "2") (pinfunction "NC1_2") (pintype "passive"))
    )
    (net (code "25") (name "Net-(K5-NO1)") (class "Default")
      (node (ref "J13") (pin "1") (pinfunction "1_1") (pintype "passive"))
      (node (ref "K5") (pin "4") (pinfunction "NO1_4") (pintype "passive"))
    )
    (net (code "26") (name "Net-(K6-COM1)") (class "Default")
      (node (ref "J16") (pin "1") (pinfunction "1_1") (pintype "passive"))
      (node (ref "K6") (pin "3") (pinfunction "COM1_3") (pintype "passive"))
    )
    (net (code "27") (name "Net-(K6-NC1)") (class "Default")
      (node (ref "J18") (pin "1") (pinfunction "1_1") (pintype "passive"))
      (node (ref "K6") (pin "2") (pinfunction "NC1_2") (pintype "passive"))
    )
    (net (code "28") (name "Net-(K6-NO1)") (class "Default")
      (node (ref "J14") (pin "1") (pinfunction "1_1") (pintype "passive"))
      (node (ref "K6") (pin "4") (pinfunction "NO1_4") (pintype "passive"))
    )
    (net (code "29") (name "Net-(K7-COM1)") (class "Default")
      (node (ref "J21") (pin "1") (pinfunction "1_1") (pintype "passive"))
      (node (ref "K7") (pin "3") (pinfunction "COM1_3") (pintype "passive"))
    )
    (net (code "30") (name "Net-(K7-NC1)") (class "Default")
      (node (ref "J22") (pin "1") (pinfunction "1_1") (pintype "passive"))
      (node (ref "K7") (pin "2") (pinfunction "NC1_2") (pintype "passive"))
    )
    (net (code "31") (name "Net-(K7-NO1)") (class "Default")
      (node (ref "J20") (pin "1") (pinfunction "1_1") (pintype "passive"))
      (node (ref "K7") (pin "4") (pinfunction "NO1_4") (pintype "passive"))
    )
    (net (code "32") (name "Net-(LD1-PadC)") (class "Default")
      (node (ref "LD1") (pin "C") (pinfunction "C_C") (pintype "passive"))
      (node (ref "R5") (pin "2") (pinfunction "2_2") (pintype "passive"))
    )
    (net (code "33") (name "Net-(LD2-PadC)") (class "Default")
      (node (ref "LD2") (pin "C") (pinfunction "C_C") (pintype "passive"))
      (node (ref "R6") (pin "2") (pinfunction "2_2") (pintype "passive"))
    )
    (net (code "34") (name "Net-(LD3-PadC)") (class "Default")
      (node (ref "LD3") (pin "C") (pinfunction "C_C") (pintype "passive"))
      (node (ref "R7") (pin "2") (pinfunction "2_2") (pintype "passive"))
    )
    (net (code "35") (name "Net-(LD4-PadC)") (class "Default")
      (node (ref "LD4") (pin "C") (pinfunction "C_C") (pintype "passive"))
      (node (ref "R8") (pin "2") (pinfunction "2_2") (pintype "passive"))
    )
    (net (code "36") (name "Net-(LD5-PadC)") (class "Default")
      (node (ref "LD5") (pin "C") (pinfunction "C_C") (pintype "passive"))
      (node (ref "R9") (pin "2") (pinfunction "2_2") (pintype "passive"))
    )
    (net (code "37") (name "Net-(LD6-PadC)") (class "Default")
      (node (ref "LD6") (pin "C") (pinfunction "C_C") (pintype "passive"))
      (node (ref "R10") (pin "2") (pinfunction "2_2") (pintype "passive"))
    )
    (net (code "38") (name "Net-(LD7-C_GN)") (class "Default")
      (node (ref "LD7") (pin "3") (pinfunction "C_GN_3") (pintype "passive"))
      (node (ref "R12") (pin "2") (pinfunction "2_2") (pintype "passive"))
    )
    (net (code "39") (name "Net-(LD7-C_RED)") (class "Default")
      (node (ref "LD7") (pin "4") (pinfunction "C_RED_4") (pintype "passive"))
      (node (ref "R11") (pin "2") (pinfunction "2_2") (pintype "passive"))
    )
    (net (code "40") (name "Net-(LD8-PadC)") (class "Default")
      (node (ref "LD8") (pin "C") (pinfunction "C_C") (pintype "passive"))
      (node (ref "R13") (pin "2") (pinfunction "2_2") (pintype "passive"))
    )
    (net (code "41") (name "Net-(U2B-AVCC)") (class "Default")
      (node (ref "C2") (pin "2") (pinfunction "2_2") (pintype "passive"))
      (node (ref "C3") (pin "2") (pinfunction "2_2") (pintype "passive"))
      (node (ref "L1") (pin "1") (pinfunction "1_1") (pintype "passive"))
      (node (ref "U2") (pin "32") (pinfunction "AVCC_32") (pintype "power_in"))
    )
    (net (code "42") (name "Net-(U3-USBDM)") (class "Default")
      (node (ref "R3") (pin "2") (pinfunction "2_2") (pintype "passive"))
      (node (ref "U3") (pin "1") (pinfunction "USBDM_1") (pintype "input"))
    )
    (net (code "43") (name "Net-(U3-USBDP)") (class "Default")
      (node (ref "R4") (pin "2") (pinfunction "2_2") (pintype "passive"))
      (node (ref "U3") (pin "12") (pinfunction "USBDP_12") (pintype "input"))
    )
    (net (code "44") (name "Net-(U3-~{RESET})") (class "Default")
      (node (ref "C8") (pin "1") (pinfunction "1_1") (pintype "passive"))
      (node (ref "R1") (pin "1") (pinfunction "1_1") (pintype "passive"))
      (node (ref "R2") (pin "2") (pinfunction "2_2") (pintype "passive"))
      (node (ref "U3") (pin "2") (pinfunction "~{RESET}_2") (pintype "input"))
    )
    (net (code "45") (name "PDI_DATA") (class "Default")
      (node (ref "JP1") (pin "1") (pinfunction "PDI_DATA_1") (pintype "open_collector"))
      (node (ref "U2") (pin "7") (pinfunction "PDI_DATA_7") (pintype "bidirectional"))
    )
    (net (code "46") (name "R1_STATUS") (class "Default")
      (node (ref "K1") (pin "6") (pinfunction "COM2_6") (pintype "passive"))
      (node (ref "LD1") (pin "A") (pinfunction "A_A") (pintype "passive"))
      (node (ref "U4") (pin "1") (pinfunction "IN1_1") (pintype "input"))
    )
    (net (code "47") (name "R2_STATUS") (class "Default")
      (node (ref "K3") (pin "6") (pinfunction "COM2_6") (pintype "passive"))
      (node (ref "LD3") (pin "A") (pinfunction "A_A") (pintype "passive"))
      (node (ref "U4") (pin "2") (pinfunction "IN2_2") (pintype "input"))
    )
    (net (code "48") (name "R3_STATUS") (class "Default")
      (node (ref "K5") (pin "6") (pinfunction "COM2_6") (pintype "passive"))
      (node (ref "LD5") (pin "A") (pinfunction "A_A") (pintype "passive"))
      (node (ref "U4") (pin "3") (pinfunction "IN3_3") (pintype "input"))
    )
    (net (code "49") (name "R4_STATUS") (class "Default")
      (node (ref "K7") (pin "6") (pinfunction "COM2_6") (pintype "passive"))
      (node (ref "LD8") (pin "A") (pinfunction "A_A") (pintype "passive"))
      (node (ref "U4") (pin "4") (pinfunction "IN4_4") (pintype "input"))
    )
    (net (code "50") (name "R5_STATUS") (class "Default")
      (node (ref "K2") (pin "6") (pinfunction "COM2_6") (pintype "passive"))
      (node (ref "LD2") (pin "A") (pinfunction "A_A") (pintype "passive"))
      (node (ref "U4") (pin "5") (pinfunction "IN5_5") (pintype "input"))
    )
    (net (code "51") (name "R6_STATUS") (class "Default")
      (node (ref "K4") (pin "6") (pinfunction "COM2_6") (pintype "passive"))
      (node (ref "LD4") (pin "A") (pinfunction "A_A") (pintype "passive"))
      (node (ref "U4") (pin "6") (pinfunction "IN6_6") (pintype "input"))
    )
    (net (code "52") (name "R7_STATUS") (class "Default")
      (node (ref "K6") (pin "6") (pinfunction "COM2_6") (pintype "passive"))
      (node (ref "LD6") (pin "A") (pinfunction "A_A") (pintype "passive"))
      (node (ref "U4") (pin "7") (pinfunction "IN7_7") (pintype "input"))
    )
    (net (code "53") (name "RELAY@PA1") (class "Default")
      (node (ref "U2") (pin "19") (pinfunction "PR1_19") (pintype "bidirectional"))
      (node (ref "U5") (pin "7") (pinfunction "IN7_7") (pintype "input"))
    )
    (net (code "54") (name "RELAY@PA2") (class "Default")
      (node (ref "U2") (pin "20") (pinfunction "PR0_20") (pintype "bidirectional"))
      (node (ref "U5") (pin "6") (pinfunction "IN6_6") (pintype "input"))
    )
    (net (code "55") (name "RELAY@PA3") (class "Default")
      (node (ref "U2") (pin "21") (pinfunction "PD7_21") (pintype "bidirectional"))
      (node (ref "U5") (pin "5") (pinfunction "IN5_5") (pintype "input"))
    )
    (net (code "56") (name "RELAY@PA4") (class "Default")
      (node (ref "U2") (pin "22") (pinfunction "PD6_22") (pintype "bidirectional"))
      (node (ref "U5") (pin "4") (pinfunction "IN4_4") (pintype "input"))
    )
    (net (code "57") (name "RELAY@PA5") (class "Default")
      (node (ref "U2") (pin "23") (pinfunction "PD5_23") (pintype "bidirectional"))
      (node (ref "U5") (pin "3") (pinfunction "IN3_3") (pintype "input"))
    )
    (net (code "58") (name "RELAY@PA6") (class "Default")
      (node (ref "U2") (pin "24") (pinfunction "PD4_24") (pintype "bidirectional"))
      (node (ref "U5") (pin "2") (pinfunction "IN2_2") (pintype "input"))
    )
    (net (code "59") (name "RELAY@PA7") (class "Default")
      (node (ref "U2") (pin "27") (pinfunction "PD1_27") (pintype "bidirectional"))
      (node (ref "U5") (pin "1") (pinfunction "IN1_1") (pintype "input"))
    )
    (net (code "60") (name "RELAY_1") (class "Default")
      (node (ref "K1") (pin "8") (pinfunction "K-_8") (pintype "passive"))
      (node (ref "U5") (pin "10") (pinfunction "OUT7_10") (pintype "open_collector"))
    )
    (net (code "61") (name "RELAY_2") (class "Default")
      (node (ref "K3") (pin "8") (pinfunction "K-_8") (pintype "passive"))
      (node (ref "U5") (pin "11") (pinfunction "OUT6_11") (pintype "open_collector"))
    )
    (net (code "62") (name "RELAY_3") (class "Default")
      (node (ref "K5") (pin "8") (pinfunction "K-_8") (pintype "passive"))
      (node (ref "U5") (pin "12") (pinfunction "OUT5_12") (pintype "open_collector"))
    )
    (net (code "63") (name "RELAY_4") (class "Default")
      (node (ref "K7") (pin "8") (pinfunction "K-_8") (pintype "passive"))
      (node (ref "U5") (pin "13") (pinfunction "OUT4_13") (pintype "open_collector"))
    )
    (net (code "64") (name "RELAY_5") (class "Default")
      (node (ref "K2") (pin "8") (pinfunction "K-_8") (pintype "passive"))
      (node (ref "U5") (pin "14") (pinfunction "OUT3_14") (pintype "open_collector"))
    )
    (net (code "65") (name "RELAY_6") (class "Default")
      (node (ref "K4") (pin "8") (pinfunction "K-_8") (pintype "passive"))
      (node (ref "U5") (pin "15") (pinfunction "OUT2_15") (pintype "open_collector"))
    )
    (net (code "66") (name "RELAY_7") (class "Default")
      (node (ref "K6") (pin "8") (pinfunction "K-_8") (pintype "passive"))
      (node (ref "U5") (pin "16") (pinfunction "OUT1_16") (pintype "open_collector"))
    )
    (net (code "67") (name "RXD") (class "Default")
      (node (ref "U2") (pin "25") (pinfunction "PD3_25") (pintype "bidirectional"))
      (node (ref "U3") (pin "7") (pinfunction "TXD_7") (pintype "output"))
    )
    (net (code "68") (name "SHIELD") (class "Default")
      (node (ref "BR1") (pin "A") (pinfunction "A_A") (pintype "passive"))
      (node (ref "JU1") (pin "SH1") (pinfunction "SH1_SH1") (pintype "passive"))
      (node (ref "JU1") (pin "SH2") (pinfunction "SH1_SH2") (pintype "passive"))
    )
    (net (code "69") (name "SPARE@PA7") (class "Default")
      (node (ref "U2") (pin "29") (pinfunction "PA7_29") (pintype "bidirectional"))
    )
    (net (code "70") (name "SPARE@PC0") (class "Default")
      (node (ref "U2") (pin "16") (pinfunction "PC0_16") (pintype "bidirectional"))
    )
    (net (code "71") (name "SPARE@PD0") (class "Default")
      (node (ref "U2") (pin "28") (pinfunction "PD0_28") (pintype "bidirectional"))
    )
    (net (code "72") (name "STAT_R1") (class "Default")
      (node (ref "U2") (pin "9") (pinfunction "PC7_9") (pintype "bidirectional"))
      (node (ref "U4") (pin "16") (pinfunction "OUT1_16") (pintype "open_collector"))
    )
    (net (code "73") (name "STAT_R2") (class "Default")
      (node (ref "U2") (pin "10") (pinfunction "PC6_10") (pintype "bidirectional"))
      (node (ref "U4") (pin "15") (pinfunction "OUT2_15") (pintype "open_collector"))
    )
    (net (code "74") (name "STAT_R3") (class "Default")
      (node (ref "U2") (pin "11") (pinfunction "PC5_11") (pintype "bidirectional"))
      (node (ref "U4") (pin "14") (pinfunction "OUT3_14") (pintype "open_collector"))
    )
    (net (code "75") (name "STAT_R4") (class "Default")
      (node (ref "U2") (pin "12") (pinfunction "PC4_12") (pintype "bidirectional"))
      (node (ref "U4") (pin "13") (pinfunction "OUT4_13") (pintype "open_collector"))
    )
    (net (code "76") (name "STAT_R5") (class "Default")
      (node (ref "U2") (pin "13") (pinfunction "PC3_13") (pintype "bidirectional"))
      (node (ref "U4") (pin "12") (pinfunction "OUT5_12") (pintype "open_collector"))
    )
    (net (code "77") (name "STAT_R6") (class "Default")
      (node (ref "U2") (pin "14") (pinfunction "PC2_14") (pintype "bidirectional"))
      (node (ref "U4") (pin "11") (pinfunction "OUT6_11") (pintype "open_collector"))
    )
    (net (code "78") (name "STAT_R7") (class "Default")
      (node (ref "U2") (pin "15") (pinfunction "PC1_15") (pintype "bidirectional"))
      (node (ref "U4") (pin "10") (pinfunction "OUT7_10") (pintype "open_collector"))
    )
    (net (code "79") (name "TP1") (class "Default")
      (node (ref "TP1") (pin "1") (pinfunction "1_1") (pintype "passive"))
      (node (ref "U2") (pin "2") (pinfunction "PA4_2") (pintype "bidirectional"))
    )
    (net (code "80") (name "TP2") (class "Default")
      (node (ref "TP2") (pin "1") (pinfunction "1_1") (pintype "passive"))
      (node (ref "U2") (pin "3") (pinfunction "PA3_3") (pintype "bidirectional"))
    )
    (net (code "81") (name "TP3") (class "Default")
      (node (ref "TP3") (pin "1") (pinfunction "1_1") (pintype "passive"))
      (node (ref "U2") (pin "4") (pinfunction "PA2_4") (pintype "bidirectional"))
    )
    (net (code "82") (name "TP4") (class "Default")
      (node (ref "TP4") (pin "1") (pinfunction "1_1") (pintype "passive"))
      (node (ref "U2") (pin "5") (pinfunction "PA1_5") (pintype "bidirectional"))
    )
    (net (code "83") (name "TP5") (class "Default")
      (node (ref "TP5") (pin "1") (pinfunction "1_1") (pintype "passive"))
      (node (ref "U2") (pin "6") (pinfunction "PA0_6") (pintype "bidirectional"))
    )
    (net (code "84") (name "TXD") (class "Default")
      (node (ref "U2") (pin "26") (pinfunction "PD2_26") (pintype "bidirectional"))
      (node (ref "U3") (pin "10") (pinfunction "RXD_10") (pintype "input"))
    )
    (net (code "85") (name "V+3V3") (class "Default")
      (node (ref "C1") (pin "2") (pinfunction "2_2") (pintype "passive"))
      (node (ref "C9") (pin "2") (pinfunction "2_2") (pintype "passive"))
      (node (ref "JP1") (pin "2") (pinfunction "VTG_2") (pintype "passive"))
      (node (ref "L1") (pin "2") (pinfunction "2_2") (pintype "passive"))
      (node (ref "LD7") (pin "1") (pinfunction "A_GN_1") (pintype "passive"))
      (node (ref "LD7") (pin "2") (pinfunction "A_RED_2") (pintype "passive"))
      (node (ref "U2") (pin "17") (pinfunction "VCC_17") (pintype "power_in"))
      (node (ref "U3") (pin "3") (pinfunction "3V3OUT_3") (pintype "power_in"))
      (node (ref "U3") (pin "9") (pinfunction "VCCIO_9") (pintype "power_in"))
      (node (ref "U4") (pin "9") (pinfunction "CFW_9") (pintype "passive"))
    )
    (net (code "86") (name "unconnected-(PCB1-PadP$1)") (class "Default")
      (node (ref "PCB1") (pin "P$1") (pinfunction "P$1_P$1") (pintype "passive"))
    )
    (net (code "87") (name "unconnected-(PCB1B-P$1-PadP$2)") (class "Default")
      (node (ref "PCB1") (pin "P$2") (pinfunction "P$1_P$2") (pintype "passive"))
    )
    (net (code "88") (name "unconnected-(PCB1C-P$1-PadP$3)") (class "Default")
      (node (ref "PCB1") (pin "P$3") (pinfunction "P$1_P$3") (pintype "passive"))
    )
    (net (code "89") (name "unconnected-(PCB1D-P$1-PadP$4)") (class "Default")
      (node (ref "PCB1") (pin "P$4") (pinfunction "P$1_P$4") (pintype "passive"))
    )
    (net (code "90") (name "unconnected-(U3-CBUS0-Pad6)") (class "Default")
      (node (ref "U3") (pin "6") (pinfunction "CBUS0_6") (pintype "bidirectional"))
    )
    (net (code "91") (name "unconnected-(U3-~{CTS}-Pad11)") (class "Default")
      (node (ref "U3") (pin "11") (pinfunction "~{CTS}_11") (pintype "input"))
    )
    (net (code "92") (name "unconnected-(U3-~{RTS}-Pad8)") (class "Default")
      (node (ref "U3") (pin "8") (pinfunction "~{RTS}_8") (pintype "output"))
    )
  )
)
